# CanFaults.net
KiCad netlist of a schematic drawn in Altium Designer
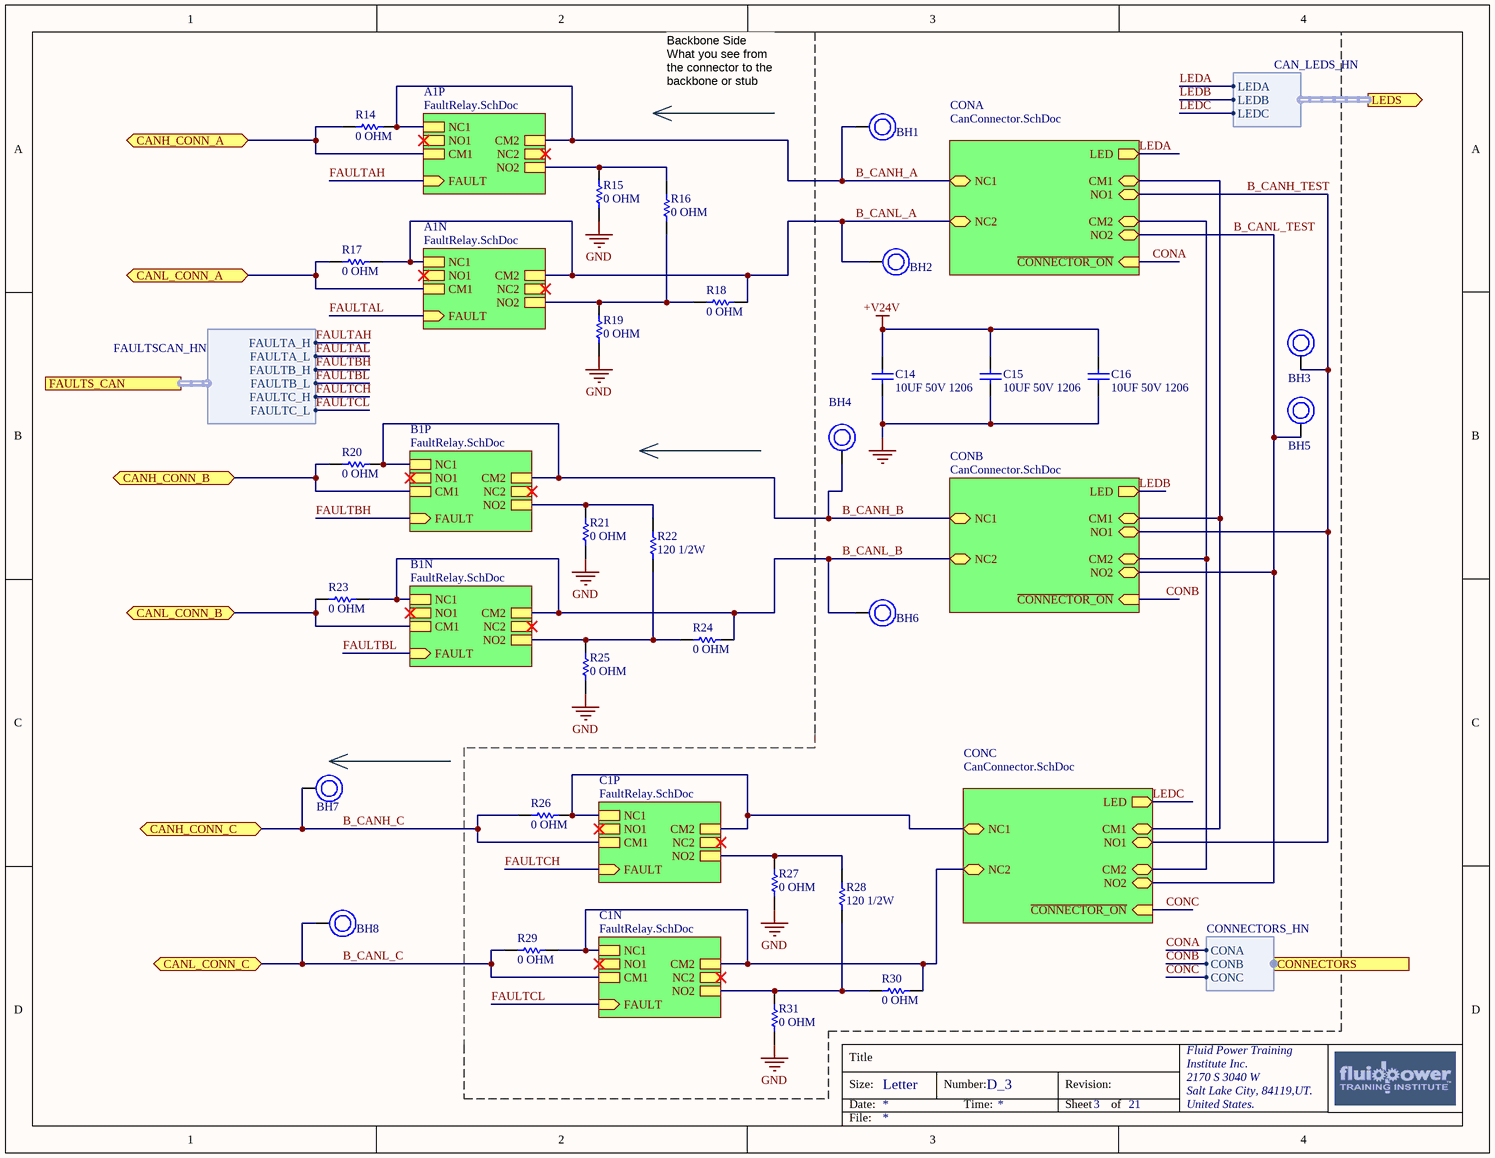
[diagram p0: CanFaults.SchDoc]

(export (version "E")
  (design (tool "Eeschema 10.0.6"))
  (components
    (comp (ref "BH1")
      (value "BananaHole")
      (footprint "MC1:BananaHole")
      (description "Banana hole for panel testing and board mounting")
      (libsource (lib "MC1") (part "BananaHole"))
    )
    (comp (ref "BH2")
      (value "BananaHole")
      (footprint "MC1:BananaHole")
      (description "Banana hole for panel testing and board mounting")
      (libsource (lib "MC1") (part "BananaHole"))
    )
    (comp (ref "BH3")
      (value "BananaHole")
      (footprint "MC1:BananaHole")
      (description "Banana hole for panel testing and board mounting")
      (libsource (lib "MC1") (part "BananaHole"))
    )
    (comp (ref "BH4")
      (value "BananaHole")
      (footprint "MC1:BananaHole")
      (description "Banana hole for panel testing and board mounting")
      (libsource (lib "MC1") (part "BananaHole"))
    )
    (comp (ref "BH5")
      (value "BananaHole")
      (footprint "MC1:BananaHole")
      (description "Banana hole for panel testing and board mounting")
      (libsource (lib "MC1") (part "BananaHole"))
    )
    (comp (ref "BH6")
      (value "BananaHole")
      (footprint "MC1:BananaHole")
      (description "Banana hole for panel testing and board mounting")
      (libsource (lib "MC1") (part "BananaHole"))
    )
    (comp (ref "BH7")
      (value "BananaHole")
      (footprint "MC1:BananaHole")
      (description "Banana hole for panel testing and board mounting")
      (libsource (lib "MC1") (part "BananaHole"))
    )
    (comp (ref "BH8")
      (value "BananaHole")
      (footprint "MC1:BananaHole")
      (description "Banana hole for panel testing and board mounting")
      (libsource (lib "MC1") (part "BananaHole"))
    )
    (comp (ref "C14")
      (value "10UF 50V 1206")
      (footprint "MC1:CAPC3216X180X20ML20")
      (description "CAP CER 10UF 50V X5R 1206")
      (fields
        (field (name "MANUFACTURER") "TDK")
        (field (name "MANUFACTURER PART NUMBER") "C3216X5R1H106K160AB")
      )
      (libsource (lib "MC1") (part "C3216X5R1H106K160AB"))
    )
    (comp (ref "C15")
      (value "10UF 50V 1206")
      (footprint "MC1:CAPC3216X180X20ML20")
      (description "CAP CER 10UF 50V X5R 1206")
      (fields
        (field (name "MANUFACTURER") "TDK")
        (field (name "MANUFACTURER PART NUMBER") "C3216X5R1H106K160AB")
      )
      (libsource (lib "MC1") (part "C3216X5R1H106K160AB"))
    )
    (comp (ref "C16")
      (value "10UF 50V 1206")
      (footprint "MC1:CAPC3216X180X20ML20")
      (description "CAP CER 10UF 50V X5R 1206")
      (fields
        (field (name "MANUFACTURER") "TDK")
        (field (name "MANUFACTURER PART NUMBER") "C3216X5R1H106K160AB")
      )
      (libsource (lib "MC1") (part "C3216X5R1H106K160AB"))
    )
    (comp (ref "R14")
      (value "0 OHM")
      (footprint "R0805")
      (description "Res Thick Film 0805 0 Ohm Pad SMD Automotive T/R")
      (fields
        (field (name "MANUFACTURER") "KOA Speer")
        (field (name "MANUFACTURER PART NUMBER") "RK73Z2ATTD")
      )
      (libsource (lib "MCx") (part "RK73Z2ATTD"))
    )
    (comp (ref "R15")
      (value "0 OHM")
      (footprint "R0805")
      (description "Res Thick Film 0805 0 Ohm Pad SMD Automotive T/R")
      (fields
        (field (name "MANUFACTURER") "KOA Speer")
        (field (name "MANUFACTURER PART NUMBER") "RK73Z2ATTD")
      )
      (libsource (lib "MCx") (part "RK73Z2ATTD"))
    )
    (comp (ref "R16")
      (value "0 OHM")
      (footprint "R0805")
      (description "Res Thick Film 0805 0 Ohm Pad SMD Automotive T/R")
      (fields
        (field (name "MANUFACTURER") "KOA Speer")
        (field (name "MANUFACTURER PART NUMBER") "RK73Z2ATTD")
      )
      (libsource (lib "MCx") (part "RK73Z2ATTD"))
    )
    (comp (ref "R17")
      (value "0 OHM")
      (footprint "R0805")
      (description "Res Thick Film 0805 0 Ohm Pad SMD Automotive T/R")
      (fields
        (field (name "MANUFACTURER") "KOA Speer")
        (field (name "MANUFACTURER PART NUMBER") "RK73Z2ATTD")
      )
      (libsource (lib "MCx") (part "RK73Z2ATTD"))
    )
    (comp (ref "R18")
      (value "0 OHM")
      (footprint "R0805")
      (description "Res Thick Film 0805 0 Ohm Pad SMD Automotive T/R")
      (fields
        (field (name "MANUFACTURER") "KOA Speer")
        (field (name "MANUFACTURER PART NUMBER") "RK73Z2ATTD")
      )
      (libsource (lib "MCx") (part "RK73Z2ATTD"))
    )
    (comp (ref "R19")
      (value "0 OHM")
      (footprint "R0805")
      (description "Res Thick Film 0805 0 Ohm Pad SMD Automotive T/R")
      (fields
        (field (name "MANUFACTURER") "KOA Speer")
        (field (name "MANUFACTURER PART NUMBER") "RK73Z2ATTD")
      )
      (libsource (lib "MCx") (part "RK73Z2ATTD"))
    )
    (comp (ref "R20")
      (value "0 OHM")
      (footprint "R0805")
      (description "Res Thick Film 0805 0 Ohm Pad SMD Automotive T/R")
      (fields
        (field (name "MANUFACTURER") "KOA Speer")
        (field (name "MANUFACTURER PART NUMBER") "RK73Z2ATTD")
      )
      (libsource (lib "MCx") (part "RK73Z2ATTD"))
    )
    (comp (ref "R21")
      (value "0 OHM")
      (footprint "R0805")
      (description "Res Thick Film 0805 0 Ohm Pad SMD Automotive T/R")
      (fields
        (field (name "MANUFACTURER") "KOA Speer")
        (field (name "MANUFACTURER PART NUMBER") "RK73Z2ATTD")
      )
      (libsource (lib "MCx") (part "RK73Z2ATTD"))
    )
    (comp (ref "R22")
      (value "120 1/2W")
      (footprint "MC1:RESC3225X60X45NL20T20")
      (description "Thick Film Resistors - SMD 1/2watt 120ohms 1%")
      (fields
        (field (name "MANUFACTURER") "Vishay")
        (field (name "MANUFACTURER PART NUMBER") "CRCW1210120RFKEA")
      )
      (libsource (lib "MC1") (part "CRCW1210120RFKEA"))
    )
    (comp (ref "R23")
      (value "0 OHM")
      (footprint "R0805")
      (description "Res Thick Film 0805 0 Ohm Pad SMD Automotive T/R")
      (fields
        (field (name "MANUFACTURER") "KOA Speer")
        (field (name "MANUFACTURER PART NUMBER") "RK73Z2ATTD")
      )
      (libsource (lib "MCx") (part "RK73Z2ATTD"))
    )
    (comp (ref "R24")
      (value "0 OHM")
      (footprint "R0805")
      (description "Res Thick Film 0805 0 Ohm Pad SMD Automotive T/R")
      (fields
        (field (name "MANUFACTURER") "KOA Speer")
        (field (name "MANUFACTURER PART NUMBER") "RK73Z2ATTD")
      )
      (libsource (lib "MCx") (part "RK73Z2ATTD"))
    )
    (comp (ref "R25")
      (value "0 OHM")
      (footprint "R0805")
      (description "Res Thick Film 0805 0 Ohm Pad SMD Automotive T/R")
      (fields
        (field (name "MANUFACTURER") "KOA Speer")
        (field (name "MANUFACTURER PART NUMBER") "RK73Z2ATTD")
      )
      (libsource (lib "MCx") (part "RK73Z2ATTD"))
    )
    (comp (ref "R26")
      (value "0 OHM")
      (footprint "R0805")
      (description "Res Thick Film 0805 0 Ohm Pad SMD Automotive T/R")
      (fields
        (field (name "MANUFACTURER") "KOA Speer")
        (field (name "MANUFACTURER PART NUMBER") "RK73Z2ATTD")
      )
      (libsource (lib "MCx") (part "RK73Z2ATTD"))
    )
    (comp (ref "R27")
      (value "0 OHM")
      (footprint "R0805")
      (description "Res Thick Film 0805 0 Ohm Pad SMD Automotive T/R")
      (fields
        (field (name "MANUFACTURER") "KOA Speer")
        (field (name "MANUFACTURER PART NUMBER") "RK73Z2ATTD")
      )
      (libsource (lib "MCx") (part "RK73Z2ATTD"))
    )
    (comp (ref "R28")
      (value "120 1/2W")
      (footprint "MC1:RESC3225X60X45NL20T20")
      (description "Thick Film Resistors - SMD 1/2watt 120ohms 1%")
      (fields
        (field (name "MANUFACTURER") "Vishay")
        (field (name "MANUFACTURER PART NUMBER") "CRCW1210120RFKEA")
      )
      (libsource (lib "MC1") (part "CRCW1210120RFKEA"))
    )
    (comp (ref "R29")
      (value "0 OHM")
      (footprint "R0805")
      (description "Res Thick Film 0805 0 Ohm Pad SMD Automotive T/R")
      (fields
        (field (name "MANUFACTURER") "KOA Speer")
        (field (name "MANUFACTURER PART NUMBER") "RK73Z2ATTD")
      )
      (libsource (lib "MCx") (part "RK73Z2ATTD"))
    )
    (comp (ref "R30")
      (value "0 OHM")
      (footprint "R0805")
      (description "Res Thick Film 0805 0 Ohm Pad SMD Automotive T/R")
      (fields
        (field (name "MANUFACTURER") "KOA Speer")
        (field (name "MANUFACTURER PART NUMBER") "RK73Z2ATTD")
      )
      (libsource (lib "MCx") (part "RK73Z2ATTD"))
    )
    (comp (ref "R31")
      (value "0 OHM")
      (footprint "R0805")
      (description "Res Thick Film 0805 0 Ohm Pad SMD Automotive T/R")
      (fields
        (field (name "MANUFACTURER") "KOA Speer")
        (field (name "MANUFACTURER PART NUMBER") "RK73Z2ATTD")
      )
      (libsource (lib "MCx") (part "RK73Z2ATTD"))
    )
  )
  (nets
    (net (code "4") (name "+V24V") (class "Default")
      (node (ref "C14") (pin "2") (pinfunction "2_2") (pintype "passive"))
      (node (ref "C15") (pin "2") (pinfunction "2_2") (pintype "passive"))
      (node (ref "C16") (pin "2") (pinfunction "2_2") (pintype "passive"))
    )
    (net (code "5") (name "/B_CANH_A") (class "Default")
      (node (ref "BH1") (pin "1") (pinfunction "1_1") (pintype "passive"))
      (node (ref "R14") (pin "2") (pinfunction "2_2") (pintype "passive"))
    )
    (net (code "6") (name "/B_CANH_B") (class "Default")
      (node (ref "BH4") (pin "1") (pinfunction "1_1") (pintype "passive"))
      (node (ref "R20") (pin "2") (pinfunction "2_2") (pintype "passive"))
    )
    (net (code "7") (name "/B_CANH_C") (class "Default")
      (node (ref "BH7") (pin "1") (pinfunction "1_1") (pintype "passive"))
      (node (ref "R26") (pin "1") (pinfunction "1_1") (pintype "passive"))
    )
    (net (code "8") (name "/B_CANH_TEST") (class "Default")
      (node (ref "BH3") (pin "1") (pinfunction "1_1") (pintype "passive"))
    )
    (net (code "9") (name "/B_CANL_A") (class "Default")
      (node (ref "BH2") (pin "1") (pinfunction "1_1") (pintype "passive"))
      (node (ref "R17") (pin "2") (pinfunction "2_2") (pintype "passive"))
      (node (ref "R18") (pin "1") (pinfunction "1_1") (pintype "passive"))
    )
    (net (code "10") (name "/B_CANL_B") (class "Default")
      (node (ref "BH6") (pin "1") (pinfunction "1_1") (pintype "passive"))
      (node (ref "R23") (pin "2") (pinfunction "2_2") (pintype "passive"))
      (node (ref "R24") (pin "1") (pinfunction "1_1") (pintype "passive"))
    )
    (net (code "11") (name "/B_CANL_C") (class "Default")
      (node (ref "BH8") (pin "1") (pinfunction "1_1") (pintype "passive"))
      (node (ref "R29") (pin "1") (pinfunction "1_1") (pintype "passive"))
    )
    (net (code "12") (name "/B_CANL_TEST") (class "Default")
      (node (ref "BH5") (pin "1") (pinfunction "1_1") (pintype "passive"))
    )
    (net (code "13") (name "/CANH_CONN_A") (class "Default")
      (node (ref "R14") (pin "1") (pinfunction "1_1") (pintype "passive"))
    )
    (net (code "14") (name "/CANH_CONN_B") (class "Default")
      (node (ref "R20") (pin "1") (pinfunction "1_1") (pintype "passive"))
    )
    (net (code "15") (name "/CANL_CONN_A") (class "Default")
      (node (ref "R17") (pin "1") (pinfunction "1_1") (pintype "passive"))
    )
    (net (code "16") (name "/CANL_CONN_B") (class "Default")
      (node (ref "R23") (pin "1") (pinfunction "1_1") (pintype "passive"))
    )
    (net (code "18") (name "/CM2") (class "Default")
      (node (ref "R26") (pin "2") (pinfunction "2_2") (pintype "passive"))
    )
    (net (code "19") (name "/CM2_1") (class "Default")
      (node (ref "R29") (pin "2") (pinfunction "2_2") (pintype "passive"))
      (node (ref "R30") (pin "1") (pinfunction "1_1") (pintype "passive"))
    )
    (net (code "45") (name "/NO2") (class "Default")
      (node (ref "R21") (pin "2") (pinfunction "2_2") (pintype "passive"))
      (node (ref "R22") (pin "2") (pinfunction "2_2") (pintype "passive"))
    )
    (net (code "46") (name "/NO2_1") (class "Default")
      (node (ref "R15") (pin "2") (pinfunction "2_2") (pintype "passive"))
      (node (ref "R16") (pin "2") (pinfunction "2_2") (pintype "passive"))
    )
    (net (code "47") (name "/NO2_2") (class "Default")
      (node (ref "R16") (pin "1") (pinfunction "1_1") (pintype "passive"))
      (node (ref "R18") (pin "2") (pinfunction "2_2") (pintype "passive"))
      (node (ref "R19") (pin "2") (pinfunction "2_2") (pintype "passive"))
    )
    (net (code "48") (name "/NO2_3") (class "Default")
      (node (ref "R22") (pin "1") (pinfunction "1_1") (pintype "passive"))
      (node (ref "R24") (pin "2") (pinfunction "2_2") (pintype "passive"))
      (node (ref "R25") (pin "2") (pinfunction "2_2") (pintype "passive"))
    )
    (net (code "49") (name "/NO2_4") (class "Default")
      (node (ref "R27") (pin "2") (pinfunction "2_2") (pintype "passive"))
      (node (ref "R28") (pin "2") (pinfunction "2_2") (pintype "passive"))
    )
    (net (code "50") (name "/NO2_5") (class "Default")
      (node (ref "R28") (pin "1") (pinfunction "1_1") (pintype "passive"))
      (node (ref "R30") (pin "2") (pinfunction "2_2") (pintype "passive"))
      (node (ref "R31") (pin "2") (pinfunction "2_2") (pintype "passive"))
    )
    (net (code "54") (name "GND") (class "Default")
      (node (ref "C14") (pin "1") (pinfunction "1_1") (pintype "passive"))
      (node (ref "C15") (pin "1") (pinfunction "1_1") (pintype "passive"))
      (node (ref "C16") (pin "1") (pinfunction "1_1") (pintype "passive"))
      (node (ref "R15") (pin "1") (pinfunction "1_1") (pintype "passive"))
      (node (ref "R19") (pin "1") (pinfunction "1_1") (pintype "passive"))
      (node (ref "R21") (pin "1") (pinfunction "1_1") (pintype "passive"))
      (node (ref "R25") (pin "1") (pinfunction "1_1") (pintype "passive"))
      (node (ref "R27") (pin "1") (pinfunction "1_1") (pintype "passive"))
      (node (ref "R31") (pin "1") (pinfunction "1_1") (pintype "passive"))
    )
  )
)
